# 9_1wire.net
KiCad netlist of a schematic drawn in EAGLE
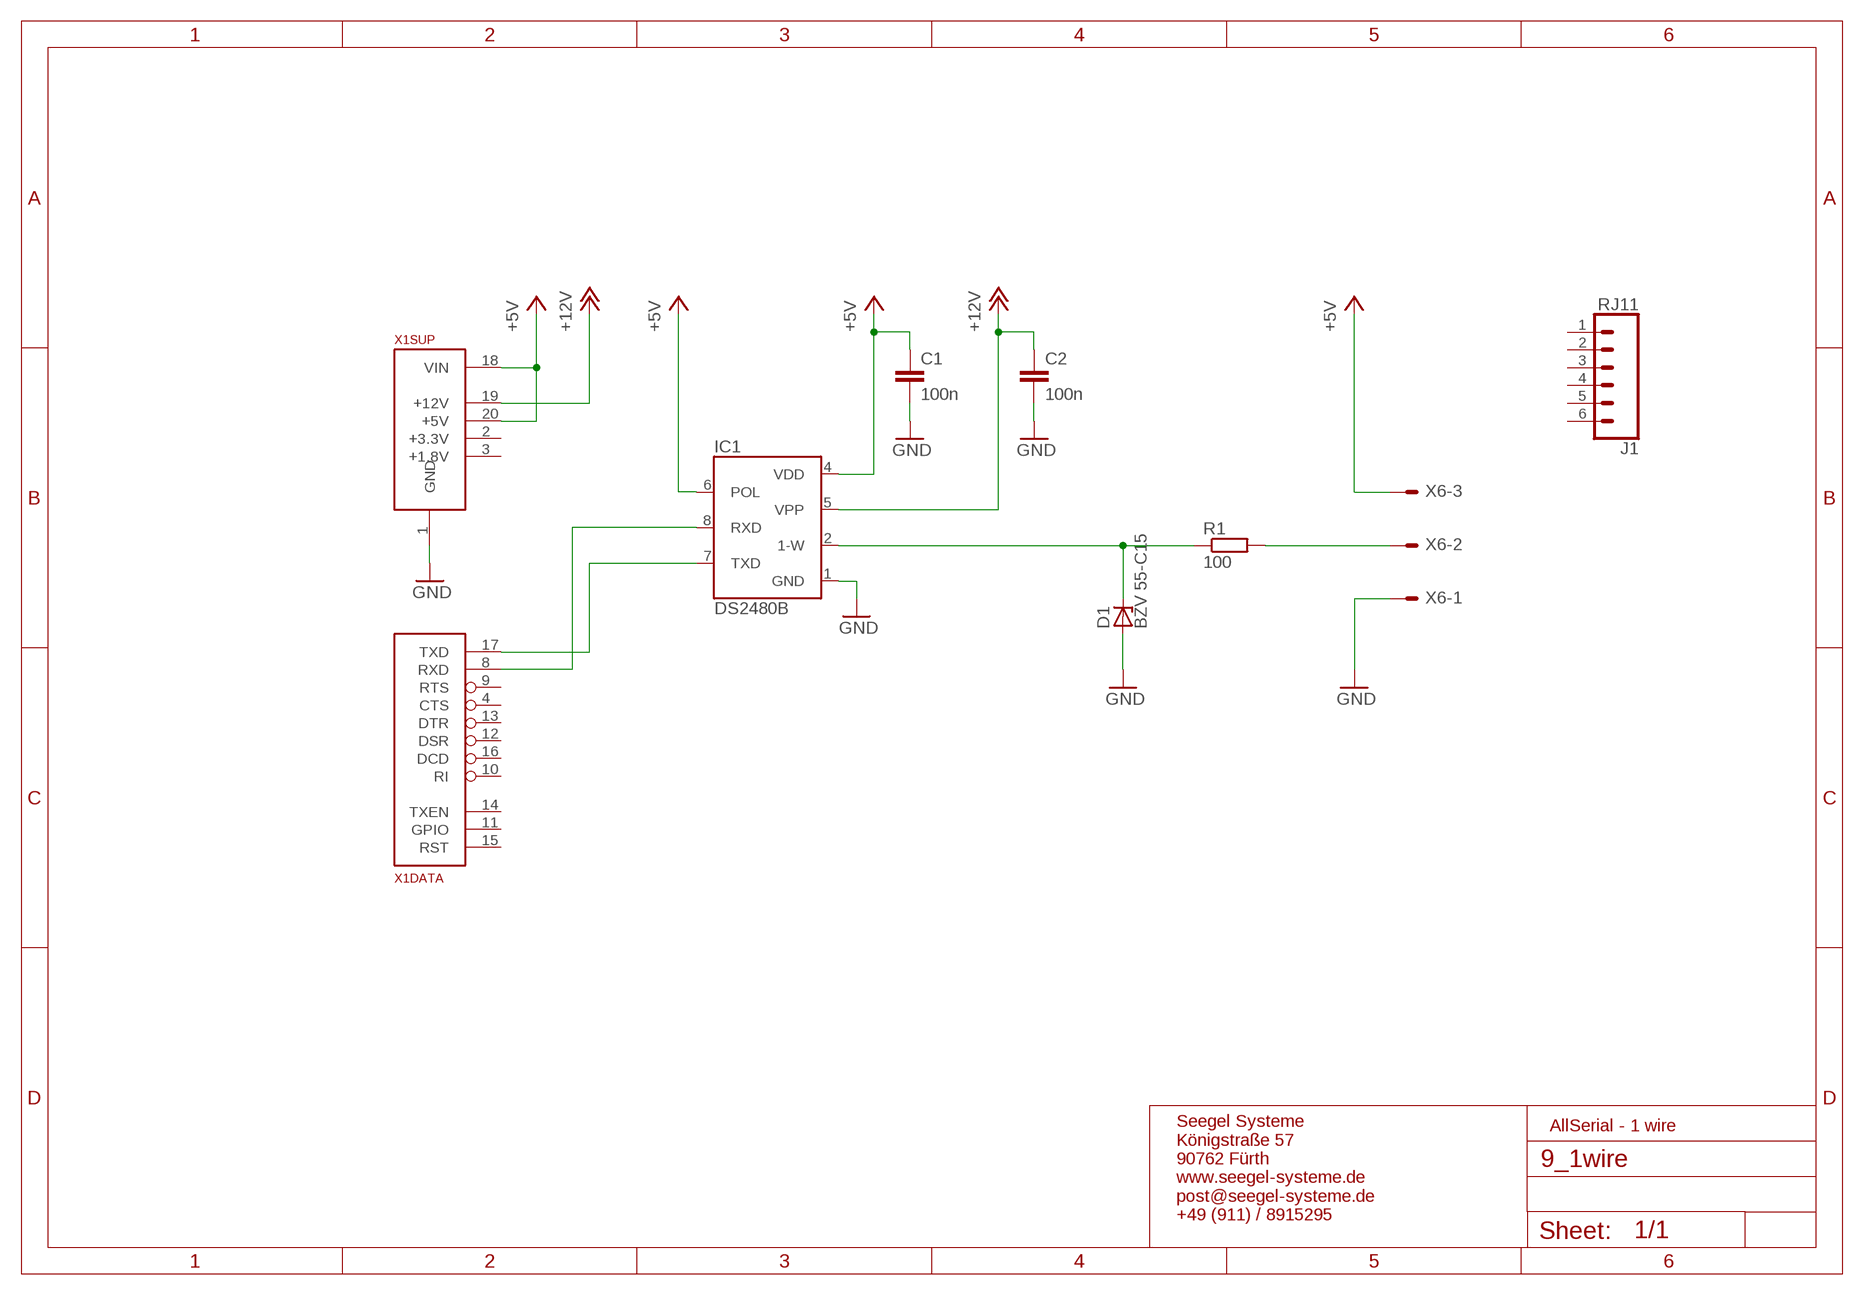
[diagram p0: schematic, sheet 1]

(export (version "E")
  (design (tool "Eeschema 10.0.6"))
  (components
    (comp (ref "C1")
      (value "100n")
      (footprint "eagle-import:C0805")
      (libsource (lib "eagle-import") (part "C-EUC0805"))
    )
    (comp (ref "C2")
      (value "100n")
      (footprint "eagle-import:C0805")
      (libsource (lib "eagle-import") (part "C-EUC0805"))
    )
    (comp (ref "D1")
      (value "BZV 55-C15")
      (footprint "eagle-import:SOD80C")
      (libsource (lib "eagle-import") (part "ZENER-DIODESOD80C"))
    )
    (comp (ref "IC1")
      (value "DS2480B")
      (footprint "eagle-import:SO08")
      (libsource (lib "eagle-import") (part "DS2480B"))
    )
    (comp (ref "J1")
      (value "RJ11")
      (footprint "eagle-import:RJ11-6")
      (libsource (lib "eagle-import") (part "RJ11-6"))
    )
    (comp (ref "R1")
      (value "100")
      (footprint "eagle-import:R0805")
      (libsource (lib "eagle-import") (part "R-EU_R0805"))
    )
    (comp (ref "X1")
      (value "ALLSERIALSLAVE")
      (footprint "eagle-import:DAUGHTER-THT")
      (libsource (lib "eagle-import") (part "ALLSERIALSLAVE"))
    )
    (comp (ref "X6")
      (value "AKL18X-03W")
      (footprint "eagle-import:AKL182-03")
      (libsource (lib "eagle-import") (part "AKL18X-03W"))
    )
  )
  (nets
    (net (code "1") (name "+5V") (class "Default")
      (node (ref "C1") (pin "1") (pinfunction "1_1") (pintype "passive"))
      (node (ref "IC1") (pin "4") (pinfunction "VDD_4") (pintype "bidirectional"))
      (node (ref "IC1") (pin "6") (pinfunction "POL_6") (pintype "bidirectional"))
      (node (ref "X1") (pin "18") (pinfunction "VIN_18") (pintype "bidirectional"))
      (node (ref "X1") (pin "20") (pinfunction "+5V_20") (pintype "bidirectional"))
      (node (ref "X6") (pin "P$3") (pinfunction "S_P$3") (pintype "passive"))
    )
    (net (code "2") (name "+12V") (class "Default")
      (node (ref "C2") (pin "1") (pinfunction "1_1") (pintype "passive"))
      (node (ref "IC1") (pin "5") (pinfunction "VPP_5") (pintype "bidirectional"))
      (node (ref "X1") (pin "19") (pinfunction "+12V_19") (pintype "bidirectional"))
    )
    (net (code "3") (name "GND") (class "Default")
      (node (ref "C1") (pin "2") (pinfunction "2_2") (pintype "passive"))
      (node (ref "C2") (pin "2") (pinfunction "2_2") (pintype "passive"))
      (node (ref "D1") (pin "A") (pinfunction "A_A") (pintype "passive"))
      (node (ref "IC1") (pin "1") (pinfunction "GND_1") (pintype "bidirectional"))
      (node (ref "X1") (pin "1") (pinfunction "GND_1") (pintype "bidirectional"))
      (node (ref "X6") (pin "P$1") (pinfunction "S_P$1") (pintype "passive"))
    )
    (net (code "4") (name "Net-(IC1-1-W)") (class "Default")
      (node (ref "D1") (pin "C") (pinfunction "C_C") (pintype "passive"))
      (node (ref "IC1") (pin "2") (pinfunction "1-W_2") (pintype "bidirectional"))
      (node (ref "R1") (pin "1") (pinfunction "1_1") (pintype "passive"))
    )
    (net (code "5") (name "Net-(IC1-RXD)") (class "Default")
      (node (ref "IC1") (pin "8") (pinfunction "RXD_8") (pintype "bidirectional"))
      (node (ref "X1") (pin "8") (pinfunction "RXD_8") (pintype "input"))
    )
    (net (code "6") (name "Net-(IC1-TXD)") (class "Default")
      (node (ref "IC1") (pin "7") (pinfunction "TXD_7") (pintype "bidirectional"))
      (node (ref "X1") (pin "17") (pinfunction "TXD_17") (pintype "output"))
    )
    (net (code "7") (name "Net-(X6B-S)") (class "Default")
      (node (ref "R1") (pin "2") (pinfunction "2_2") (pintype "passive"))
      (node (ref "X6") (pin "P$2") (pinfunction "S_P$2") (pintype "passive"))
    )
    (net (code "8") (name "unconnected-(J1-Pad1)") (class "Default")
      (node (ref "J1") (pin "1") (pinfunction "1_1") (pintype "passive"))
    )
    (net (code "9") (name "unconnected-(J1-Pad2)") (class "Default")
      (node (ref "J1") (pin "2") (pinfunction "2_2") (pintype "passive"))
    )
    (net (code "10") (name "unconnected-(J1-Pad3)") (class "Default")
      (node (ref "J1") (pin "3") (pinfunction "3_3") (pintype "passive"))
    )
    (net (code "11") (name "unconnected-(J1-Pad4)") (class "Default")
      (node (ref "J1") (pin "4") (pinfunction "4_4") (pintype "passive"))
    )
    (net (code "12") (name "unconnected-(J1-Pad5)") (class "Default")
      (node (ref "J1") (pin "5") (pinfunction "5_5") (pintype "passive"))
    )
    (net (code "13") (name "unconnected-(J1-Pad6)") (class "Default")
      (node (ref "J1") (pin "6") (pinfunction "6_6") (pintype "passive"))
    )
    (net (code "14") (name "unconnected-(X1A-CTS-Pad4)") (class "Default")
      (node (ref "X1") (pin "4") (pinfunction "CTS_4") (pintype "input"))
    )
    (net (code "15") (name "unconnected-(X1A-DCD-Pad16)") (class "Default")
      (node (ref "X1") (pin "16") (pinfunction "DCD_16") (pintype "input"))
    )
    (net (code "16") (name "unconnected-(X1A-DSR-Pad12)") (class "Default")
      (node (ref "X1") (pin "12") (pinfunction "DSR_12") (pintype "input"))
    )
    (net (code "17") (name "unconnected-(X1A-DTR-Pad13)") (class "Default")
      (node (ref "X1") (pin "13") (pinfunction "DTR_13") (pintype "output"))
    )
    (net (code "18") (name "unconnected-(X1A-GPIO-Pad11)") (class "Default")
      (node (ref "X1") (pin "11") (pinfunction "GPIO_11") (pintype "bidirectional"))
    )
    (net (code "19") (name "unconnected-(X1A-RI-Pad10)") (class "Default")
      (node (ref "X1") (pin "10") (pinfunction "RI_10") (pintype "input"))
    )
    (net (code "20") (name "unconnected-(X1A-RST-Pad15)") (class "Default")
      (node (ref "X1") (pin "15") (pinfunction "RST_15") (pintype "bidirectional"))
    )
    (net (code "21") (name "unconnected-(X1A-RTS-Pad9)") (class "Default")
      (node (ref "X1") (pin "9") (pinfunction "RTS_9") (pintype "output"))
    )
    (net (code "22") (name "unconnected-(X1A-TXEN-Pad14)") (class "Default")
      (node (ref "X1") (pin "14") (pinfunction "TXEN_14") (pintype "output"))
    )
    (net (code "23") (name "unconnected-(X1B-+1.8V-Pad3)") (class "Default")
      (node (ref "X1") (pin "3") (pinfunction "+1.8V_3") (pintype "bidirectional"))
    )
    (net (code "24") (name "unconnected-(X1B-+3.3V-Pad2)") (class "Default")
      (node (ref "X1") (pin "2") (pinfunction "+3.3V_2") (pintype "bidirectional"))
    )
  )
)
